# LC_BigOne_-_5_3A_MOSFET_for_TLC5940_3.net
KiCad netlist of a schematic drawn in Altium Designer
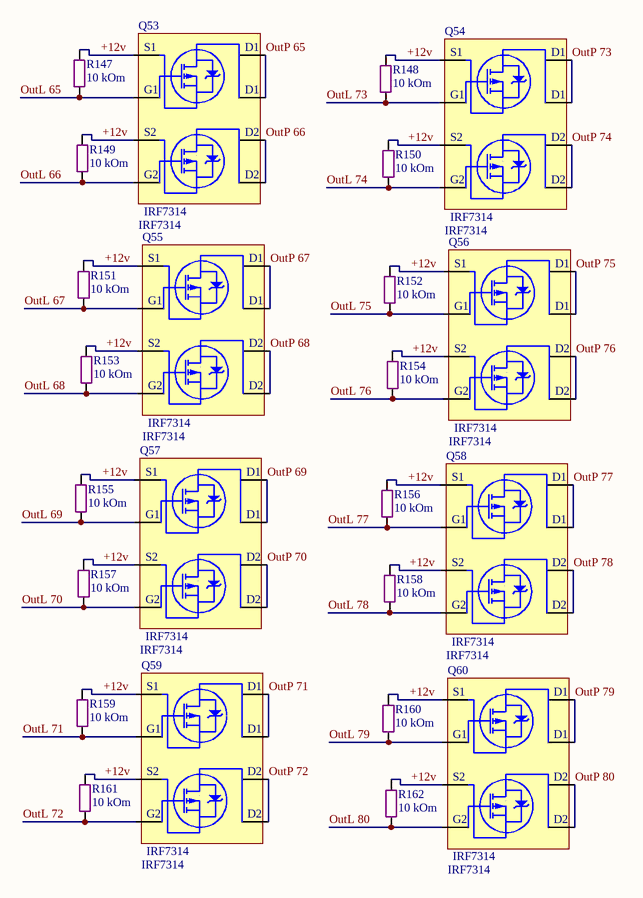
[diagram p0: LC BigOne - 5.3A MOSFET for TLC5940 3.SchDoc]

(export (version "E")
  (design (tool "Eeschema 10.0.6"))
  (components
    (comp (ref "Q53")
      (value "IRF7314")
      (footprint "GeneralCases:SO8")
      (description "Dual P-Ch  20V - 0.058Ω - 5.3A")
      (libsource (lib "Transistor") (part "IRF7314"))
    )
    (comp (ref "Q54")
      (value "IRF7314")
      (footprint "GeneralCases:SO8")
      (description "Dual P-Ch  20V - 0.058Ω - 5.3A")
      (libsource (lib "Transistor") (part "IRF7314"))
    )
    (comp (ref "Q55")
      (value "IRF7314")
      (footprint "GeneralCases:SO8")
      (description "Dual P-Ch  20V - 0.058Ω - 5.3A")
      (libsource (lib "Transistor") (part "IRF7314"))
    )
    (comp (ref "Q56")
      (value "IRF7314")
      (footprint "GeneralCases:SO8")
      (description "Dual P-Ch  20V - 0.058Ω - 5.3A")
      (libsource (lib "Transistor") (part "IRF7314"))
    )
    (comp (ref "Q57")
      (value "IRF7314")
      (footprint "GeneralCases:SO8")
      (description "Dual P-Ch  20V - 0.058Ω - 5.3A")
      (libsource (lib "Transistor") (part "IRF7314"))
    )
    (comp (ref "Q58")
      (value "IRF7314")
      (footprint "GeneralCases:SO8")
      (description "Dual P-Ch  20V - 0.058Ω - 5.3A")
      (libsource (lib "Transistor") (part "IRF7314"))
    )
    (comp (ref "Q59")
      (value "IRF7314")
      (footprint "GeneralCases:SO8")
      (description "Dual P-Ch  20V - 0.058Ω - 5.3A")
      (libsource (lib "Transistor") (part "IRF7314"))
    )
    (comp (ref "Q60")
      (value "IRF7314")
      (footprint "GeneralCases:SO8")
      (description "Dual P-Ch  20V - 0.058Ω - 5.3A")
      (libsource (lib "Transistor") (part "IRF7314"))
    )
    (comp (ref "R147")
      (value "10 kOm")
      (footprint "PassiveComponents:SMD 0805 (2012)")
      (libsource (lib "PassiveComponents") (part "Res All Types"))
    )
    (comp (ref "R148")
      (value "10 kOm")
      (footprint "PassiveComponents:SMD 0805 (2012)")
      (libsource (lib "PassiveComponents") (part "Res All Types"))
    )
    (comp (ref "R149")
      (value "10 kOm")
      (footprint "PassiveComponents:SMD 0805 (2012)")
      (libsource (lib "PassiveComponents") (part "Res All Types"))
    )
    (comp (ref "R150")
      (value "10 kOm")
      (footprint "PassiveComponents:SMD 0805 (2012)")
      (libsource (lib "PassiveComponents") (part "Res All Types"))
    )
    (comp (ref "R151")
      (value "10 kOm")
      (footprint "PassiveComponents:SMD 0805 (2012)")
      (libsource (lib "PassiveComponents") (part "Res All Types"))
    )
    (comp (ref "R152")
      (value "10 kOm")
      (footprint "PassiveComponents:SMD 0805 (2012)")
      (libsource (lib "PassiveComponents") (part "Res All Types"))
    )
    (comp (ref "R153")
      (value "10 kOm")
      (footprint "PassiveComponents:SMD 0805 (2012)")
      (libsource (lib "PassiveComponents") (part "Res All Types"))
    )
    (comp (ref "R154")
      (value "10 kOm")
      (footprint "PassiveComponents:SMD 0805 (2012)")
      (libsource (lib "PassiveComponents") (part "Res All Types"))
    )
    (comp (ref "R155")
      (value "10 kOm")
      (footprint "PassiveComponents:SMD 0805 (2012)")
      (libsource (lib "PassiveComponents") (part "Res All Types"))
    )
    (comp (ref "R156")
      (value "10 kOm")
      (footprint "PassiveComponents:SMD 0805 (2012)")
      (libsource (lib "PassiveComponents") (part "Res All Types"))
    )
    (comp (ref "R157")
      (value "10 kOm")
      (footprint "PassiveComponents:SMD 0805 (2012)")
      (libsource (lib "PassiveComponents") (part "Res All Types"))
    )
    (comp (ref "R158")
      (value "10 kOm")
      (footprint "PassiveComponents:SMD 0805 (2012)")
      (libsource (lib "PassiveComponents") (part "Res All Types"))
    )
    (comp (ref "R159")
      (value "10 kOm")
      (footprint "PassiveComponents:SMD 0805 (2012)")
      (libsource (lib "PassiveComponents") (part "Res All Types"))
    )
    (comp (ref "R160")
      (value "10 kOm")
      (footprint "PassiveComponents:SMD 0805 (2012)")
      (libsource (lib "PassiveComponents") (part "Res All Types"))
    )
    (comp (ref "R161")
      (value "10 kOm")
      (footprint "PassiveComponents:SMD 0805 (2012)")
      (libsource (lib "PassiveComponents") (part "Res All Types"))
    )
    (comp (ref "R162")
      (value "10 kOm")
      (footprint "PassiveComponents:SMD 0805 (2012)")
      (libsource (lib "PassiveComponents") (part "Res All Types"))
    )
  )
  (nets
    (net (code "1") (name "/+12v") (class "Default")
      (node (ref "Q53") (pin "1") (pinfunction "S_1") (pintype "passive"))
      (node (ref "Q53") (pin "3") (pinfunction "S_3") (pintype "passive"))
      (node (ref "Q54") (pin "1") (pinfunction "S_1") (pintype "passive"))
      (node (ref "Q54") (pin "3") (pinfunction "S_3") (pintype "passive"))
      (node (ref "Q55") (pin "1") (pinfunction "S_1") (pintype "passive"))
      (node (ref "Q55") (pin "3") (pinfunction "S_3") (pintype "passive"))
      (node (ref "Q56") (pin "1") (pinfunction "S_1") (pintype "passive"))
      (node (ref "Q56") (pin "3") (pinfunction "S_3") (pintype "passive"))
      (node (ref "Q57") (pin "1") (pinfunction "S_1") (pintype "passive"))
      (node (ref "Q57") (pin "3") (pinfunction "S_3") (pintype "passive"))
      (node (ref "Q58") (pin "1") (pinfunction "S_1") (pintype "passive"))
      (node (ref "Q58") (pin "3") (pinfunction "S_3") (pintype "passive"))
      (node (ref "Q59") (pin "1") (pinfunction "S_1") (pintype "passive"))
      (node (ref "Q59") (pin "3") (pinfunction "S_3") (pintype "passive"))
      (node (ref "Q60") (pin "1") (pinfunction "S_1") (pintype "passive"))
      (node (ref "Q60") (pin "3") (pinfunction "S_3") (pintype "passive"))
      (node (ref "R147") (pin "2") (pinfunction "2_2") (pintype "passive"))
      (node (ref "R148") (pin "2") (pinfunction "2_2") (pintype "passive"))
      (node (ref "R149") (pin "2") (pinfunction "2_2") (pintype "passive"))
      (node (ref "R150") (pin "2") (pinfunction "2_2") (pintype "passive"))
      (node (ref "R151") (pin "2") (pinfunction "2_2") (pintype "passive"))
      (node (ref "R152") (pin "2") (pinfunction "2_2") (pintype "passive"))
      (node (ref "R153") (pin "2") (pinfunction "2_2") (pintype "passive"))
      (node (ref "R154") (pin "2") (pinfunction "2_2") (pintype "passive"))
      (node (ref "R155") (pin "2") (pinfunction "2_2") (pintype "passive"))
      (node (ref "R156") (pin "2") (pinfunction "2_2") (pintype "passive"))
      (node (ref "R157") (pin "2") (pinfunction "2_2") (pintype "passive"))
      (node (ref "R158") (pin "2") (pinfunction "2_2") (pintype "passive"))
      (node (ref "R159") (pin "2") (pinfunction "2_2") (pintype "passive"))
      (node (ref "R160") (pin "2") (pinfunction "2_2") (pintype "passive"))
      (node (ref "R161") (pin "2") (pinfunction "2_2") (pintype "passive"))
      (node (ref "R162") (pin "2") (pinfunction "2_2") (pintype "passive"))
    )
    (net (code "2") (name "/OutL 65") (class "Default")
      (node (ref "Q53") (pin "2") (pinfunction "G_2") (pintype "passive"))
      (node (ref "R147") (pin "1") (pinfunction "1_1") (pintype "passive"))
    )
    (net (code "3") (name "/OutL 66") (class "Default")
      (node (ref "Q53") (pin "4") (pinfunction "G_4") (pintype "passive"))
      (node (ref "R149") (pin "1") (pinfunction "1_1") (pintype "passive"))
    )
    (net (code "4") (name "/OutL 67") (class "Default")
      (node (ref "Q55") (pin "2") (pinfunction "G_2") (pintype "passive"))
      (node (ref "R151") (pin "1") (pinfunction "1_1") (pintype "passive"))
    )
    (net (code "5") (name "/OutL 68") (class "Default")
      (node (ref "Q55") (pin "4") (pinfunction "G_4") (pintype "passive"))
      (node (ref "R153") (pin "1") (pinfunction "1_1") (pintype "passive"))
    )
    (net (code "6") (name "/OutL 69") (class "Default")
      (node (ref "Q57") (pin "2") (pinfunction "G_2") (pintype "passive"))
      (node (ref "R155") (pin "1") (pinfunction "1_1") (pintype "passive"))
    )
    (net (code "7") (name "/OutL 70") (class "Default")
      (node (ref "Q57") (pin "4") (pinfunction "G_4") (pintype "passive"))
      (node (ref "R157") (pin "1") (pinfunction "1_1") (pintype "passive"))
    )
    (net (code "8") (name "/OutL 71") (class "Default")
      (node (ref "Q59") (pin "2") (pinfunction "G_2") (pintype "passive"))
      (node (ref "R159") (pin "1") (pinfunction "1_1") (pintype "passive"))
    )
    (net (code "9") (name "/OutL 72") (class "Default")
      (node (ref "Q59") (pin "4") (pinfunction "G_4") (pintype "passive"))
      (node (ref "R161") (pin "1") (pinfunction "1_1") (pintype "passive"))
    )
    (net (code "10") (name "/OutL 73") (class "Default")
      (node (ref "Q54") (pin "2") (pinfunction "G_2") (pintype "passive"))
      (node (ref "R148") (pin "1") (pinfunction "1_1") (pintype "passive"))
    )
    (net (code "11") (name "/OutL 74") (class "Default")
      (node (ref "Q54") (pin "4") (pinfunction "G_4") (pintype "passive"))
      (node (ref "R150") (pin "1") (pinfunction "1_1") (pintype "passive"))
    )
    (net (code "12") (name "/OutL 75") (class "Default")
      (node (ref "Q56") (pin "2") (pinfunction "G_2") (pintype "passive"))
      (node (ref "R152") (pin "1") (pinfunction "1_1") (pintype "passive"))
    )
    (net (code "13") (name "/OutL 76") (class "Default")
      (node (ref "Q56") (pin "4") (pinfunction "G_4") (pintype "passive"))
      (node (ref "R154") (pin "1") (pinfunction "1_1") (pintype "passive"))
    )
    (net (code "14") (name "/OutL 77") (class "Default")
      (node (ref "Q58") (pin "2") (pinfunction "G_2") (pintype "passive"))
      (node (ref "R156") (pin "1") (pinfunction "1_1") (pintype "passive"))
    )
    (net (code "15") (name "/OutL 78") (class "Default")
      (node (ref "Q58") (pin "4") (pinfunction "G_4") (pintype "passive"))
      (node (ref "R158") (pin "1") (pinfunction "1_1") (pintype "passive"))
    )
    (net (code "16") (name "/OutL 79") (class "Default")
      (node (ref "Q60") (pin "2") (pinfunction "G_2") (pintype "passive"))
      (node (ref "R160") (pin "1") (pinfunction "1_1") (pintype "passive"))
    )
    (net (code "17") (name "/OutL 80") (class "Default")
      (node (ref "Q60") (pin "4") (pinfunction "G_4") (pintype "passive"))
      (node (ref "R162") (pin "1") (pinfunction "1_1") (pintype "passive"))
    )
    (net (code "18") (name "/OutP 65") (class "Default")
      (node (ref "Q53") (pin "7") (pinfunction "D_7") (pintype "passive"))
      (node (ref "Q53") (pin "8") (pinfunction "D_8") (pintype "passive"))
    )
    (net (code "19") (name "/OutP 66") (class "Default")
      (node (ref "Q53") (pin "5") (pinfunction "D_5") (pintype "passive"))
      (node (ref "Q53") (pin "6") (pinfunction "D_6") (pintype "passive"))
    )
    (net (code "20") (name "/OutP 67") (class "Default")
      (node (ref "Q55") (pin "7") (pinfunction "D_7") (pintype "passive"))
      (node (ref "Q55") (pin "8") (pinfunction "D_8") (pintype "passive"))
    )
    (net (code "21") (name "/OutP 68") (class "Default")
      (node (ref "Q55") (pin "5") (pinfunction "D_5") (pintype "passive"))
      (node (ref "Q55") (pin "6") (pinfunction "D_6") (pintype "passive"))
    )
    (net (code "22") (name "/OutP 69") (class "Default")
      (node (ref "Q57") (pin "7") (pinfunction "D_7") (pintype "passive"))
      (node (ref "Q57") (pin "8") (pinfunction "D_8") (pintype "passive"))
    )
    (net (code "23") (name "/OutP 70") (class "Default")
      (node (ref "Q57") (pin "5") (pinfunction "D_5") (pintype "passive"))
      (node (ref "Q57") (pin "6") (pinfunction "D_6") (pintype "passive"))
    )
    (net (code "24") (name "/OutP 71") (class "Default")
      (node (ref "Q59") (pin "7") (pinfunction "D_7") (pintype "passive"))
      (node (ref "Q59") (pin "8") (pinfunction "D_8") (pintype "passive"))
    )
    (net (code "25") (name "/OutP 72") (class "Default")
      (node (ref "Q59") (pin "5") (pinfunction "D_5") (pintype "passive"))
      (node (ref "Q59") (pin "6") (pinfunction "D_6") (pintype "passive"))
    )
    (net (code "26") (name "/OutP 73") (class "Default")
      (node (ref "Q54") (pin "7") (pinfunction "D_7") (pintype "passive"))
      (node (ref "Q54") (pin "8") (pinfunction "D_8") (pintype "passive"))
    )
    (net (code "27") (name "/OutP 74") (class "Default")
      (node (ref "Q54") (pin "5") (pinfunction "D_5") (pintype "passive"))
      (node (ref "Q54") (pin "6") (pinfunction "D_6") (pintype "passive"))
    )
    (net (code "28") (name "/OutP 75") (class "Default")
      (node (ref "Q56") (pin "7") (pinfunction "D_7") (pintype "passive"))
      (node (ref "Q56") (pin "8") (pinfunction "D_8") (pintype "passive"))
    )
    (net (code "29") (name "/OutP 76") (class "Default")
      (node (ref "Q56") (pin "5") (pinfunction "D_5") (pintype "passive"))
      (node (ref "Q56") (pin "6") (pinfunction "D_6") (pintype "passive"))
    )
    (net (code "30") (name "/OutP 77") (class "Default")
      (node (ref "Q58") (pin "7") (pinfunction "D_7") (pintype "passive"))
      (node (ref "Q58") (pin "8") (pinfunction "D_8") (pintype "passive"))
    )
    (net (code "31") (name "/OutP 78") (class "Default")
      (node (ref "Q58") (pin "5") (pinfunction "D_5") (pintype "passive"))
      (node (ref "Q58") (pin "6") (pinfunction "D_6") (pintype "passive"))
    )
    (net (code "32") (name "/OutP 79") (class "Default")
      (node (ref "Q60") (pin "7") (pinfunction "D_7") (pintype "passive"))
      (node (ref "Q60") (pin "8") (pinfunction "D_8") (pintype "passive"))
    )
    (net (code "33") (name "/OutP 80") (class "Default")
      (node (ref "Q60") (pin "5") (pinfunction "D_5") (pintype "passive"))
      (node (ref "Q60") (pin "6") (pinfunction "D_6") (pintype "passive"))
    )
  )
)
